# Front_panel.net
KiCad netlist of a schematic drawn in Altium Designer
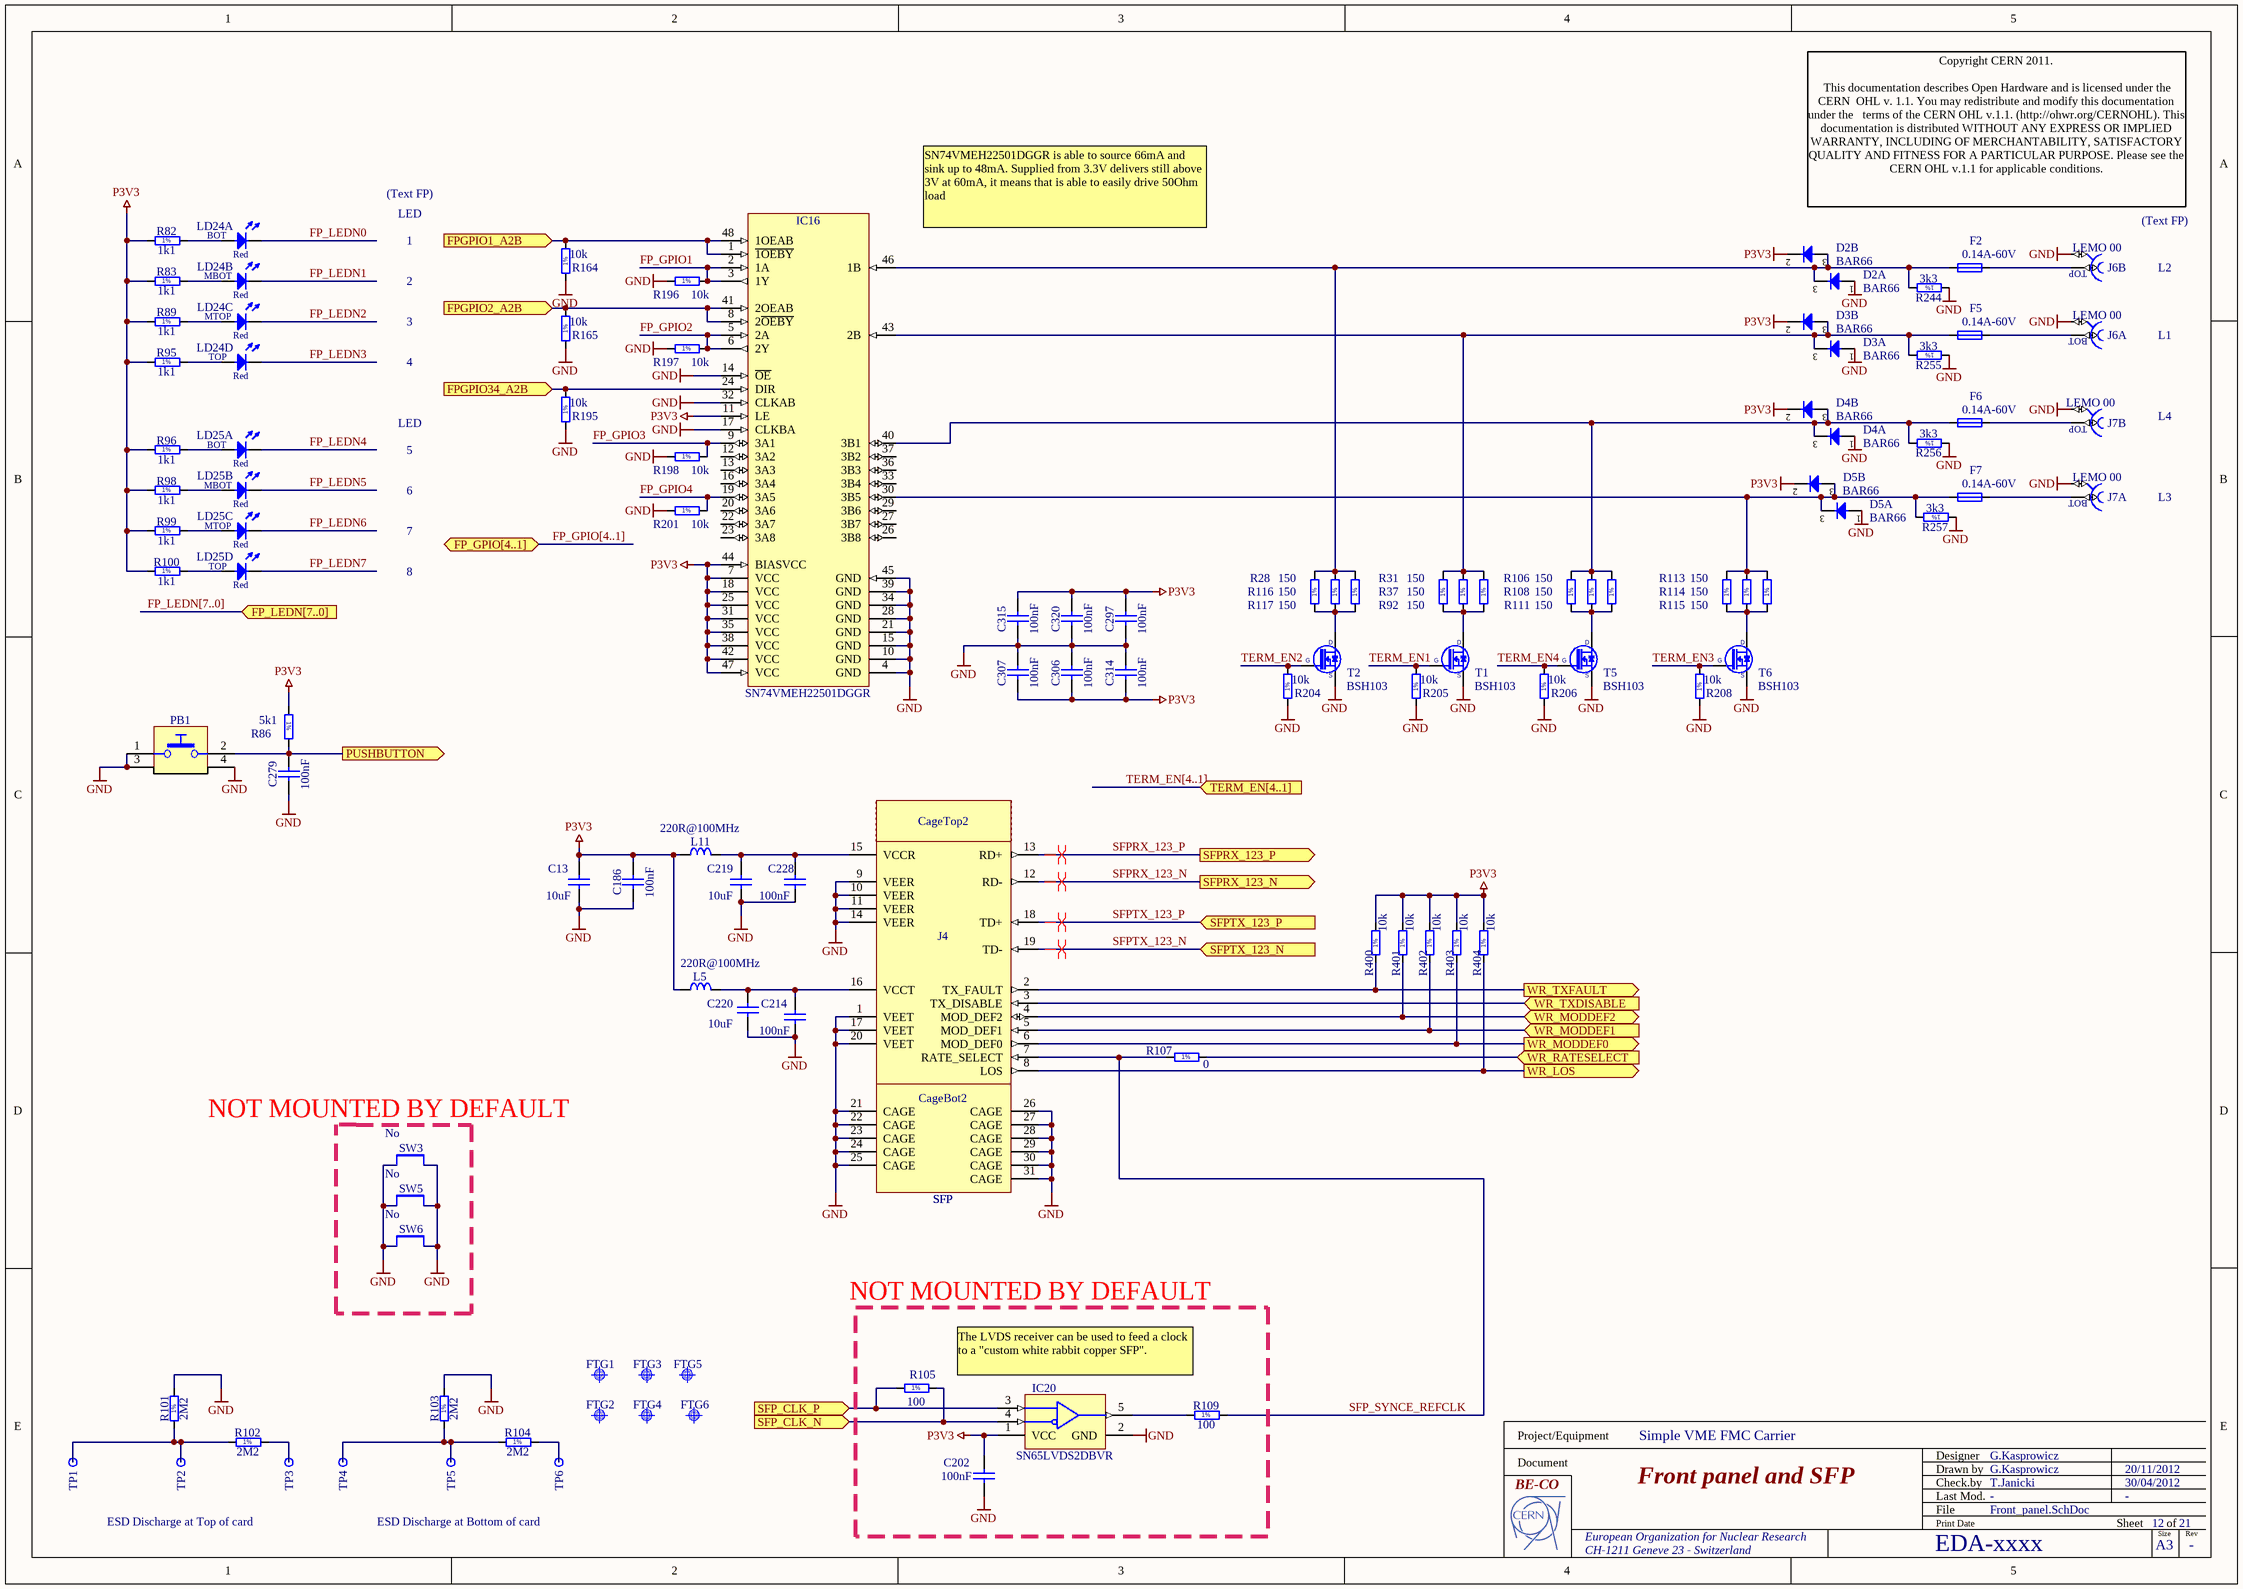
[diagram p0: Front_panel.SchDoc]

(export (version "E")
  (design (tool "Eeschema 10.0.6"))
  (components
    (comp (ref "C13")
      (value "10uF")
      (footprint "CAPC3225X270N")
      (description "Non-polarised capacitor")
      (fields (field (name "PART NUMBER") "CC1210_10UF_25V_10%_X7R") (field (name "VOLTAGE") "25V"))
      (libsource (lib "Capacitors") (part "Capacitor - non polarized"))
    )
    (comp (ref "C186")
      (value "100nF")
      (footprint "CAPC1005X55N")
      (description "Non-polarised capacitor")
      (fields (field (name "PART NUMBER") "CC0402_100NF_16V_10%_X7R") (field (name "VOLTAGE") "16V"))
      (libsource (lib "Capacitors") (part "Capacitor - non polarized"))
    )
    (comp (ref "C202")
      (value "100nF")
      (footprint "CAPC1005X55N")
      (description "Non-polarised capacitor")
      (fields (field (name "PART NUMBER") "CC0402_100NF_16V_10%_X7R") (field (name "VOLTAGE") "16V"))
      (libsource (lib "Capacitors") (part "Capacitor - non polarized"))
    )
    (comp (ref "C214")
      (value "100nF")
      (footprint "CAPC1005X55N")
      (description "Non-polarised capacitor")
      (fields (field (name "PART NUMBER") "CC0402_100NF_16V_10%_X7R") (field (name "VOLTAGE") "16V"))
      (libsource (lib "Capacitors") (part "Capacitor - non polarized"))
    )
    (comp (ref "C219")
      (value "10uF")
      (footprint "CAPC3225X270N")
      (description "Non-polarised capacitor")
      (fields (field (name "PART NUMBER") "CC1210_10UF_25V_10%_X7R") (field (name "VOLTAGE") "25V"))
      (libsource (lib "Capacitors") (part "Capacitor - non polarized"))
    )
    (comp (ref "C220")
      (value "10uF")
      (footprint "CAPC3225X270N")
      (description "Non-polarised capacitor")
      (fields (field (name "PART NUMBER") "CC1210_10UF_25V_10%_X7R") (field (name "VOLTAGE") "25V"))
      (libsource (lib "Capacitors") (part "Capacitor - non polarized"))
    )
    (comp (ref "C228")
      (value "100nF")
      (footprint "CAPC1005X55N")
      (description "Non-polarised capacitor")
      (fields (field (name "PART NUMBER") "CC0402_100NF_16V_10%_X7R") (field (name "VOLTAGE") "16V"))
      (libsource (lib "Capacitors") (part "Capacitor - non polarized"))
    )
    (comp (ref "C279")
      (value "100nF")
      (footprint "CAPC1005X55N")
      (description "Non-polarised capacitor")
      (fields (field (name "PART NUMBER") "CC0402_100NF_16V_10%_X7R") (field (name "VOLTAGE") "16V"))
      (libsource (lib "Capacitors") (part "Capacitor - non polarized"))
    )
    (comp (ref "C297")
      (value "100nF")
      (footprint "CAPC1005X55N")
      (description "Non-polarised capacitor")
      (fields (field (name "PART NUMBER") "CC0402_100NF_16V_10%_X7R") (field (name "VOLTAGE") "16V"))
      (libsource (lib "Capacitors") (part "Capacitor - non polarized"))
    )
    (comp (ref "C306")
      (value "100nF")
      (footprint "CAPC1005X55N")
      (description "Non-polarised capacitor")
      (fields (field (name "PART NUMBER") "CC0402_100NF_16V_10%_X7R") (field (name "VOLTAGE") "16V"))
      (libsource (lib "Capacitors") (part "Capacitor - non polarized"))
    )
    (comp (ref "C307")
      (value "100nF")
      (footprint "CAPC1005X55N")
      (description "Non-polarised capacitor")
      (fields (field (name "PART NUMBER") "CC0402_100NF_16V_10%_X7R") (field (name "VOLTAGE") "16V"))
      (libsource (lib "Capacitors") (part "Capacitor - non polarized"))
    )
    (comp (ref "C314")
      (value "100nF")
      (footprint "CAPC1005X55N")
      (description "Non-polarised capacitor")
      (fields (field (name "PART NUMBER") "CC0402_100NF_16V_10%_X7R") (field (name "VOLTAGE") "16V"))
      (libsource (lib "Capacitors") (part "Capacitor - non polarized"))
    )
    (comp (ref "C315")
      (value "100nF")
      (footprint "CAPC1005X55N")
      (description "Non-polarised capacitor")
      (fields (field (name "PART NUMBER") "CC0402_100NF_16V_10%_X7R") (field (name "VOLTAGE") "16V"))
      (libsource (lib "Capacitors") (part "Capacitor - non polarized"))
    )
    (comp (ref "C320")
      (value "100nF")
      (footprint "CAPC1005X55N")
      (description "Non-polarised capacitor")
      (fields (field (name "PART NUMBER") "CC0402_100NF_16V_10%_X7R") (field (name "VOLTAGE") "16V"))
      (libsource (lib "Capacitors") (part "Capacitor - non polarized"))
    )
    (comp (ref "CageBot2")
      (value "SFP")
      (footprint "TYCO_6367034-1")
      (description "SFP  Cage Bottom (Small Form-factor Pluggable)")
      (fields (field (name "PART NUMBER") "TYCO_6367034-1") (field (name "MANUFACTURER") "TYCO ELECTRONICS"))
      (libsource (lib "Connectors") (part "SFPx1_Cage Bottom"))
    )
    (comp (ref "CageTop2")
      (value "SFP")
      (footprint "TYCO_6367035-1")
      (description "SFP  Cage Top (Small Form-factor Pluggable)")
      (fields (field (name "PART NUMBER") "TYCO_6367035-1") (field (name "MANUFACTURER") "TYCO ELECTRONICS"))
      (libsource (lib "Connectors") (part "SFPx1_Cage Top"))
    )
    (comp (ref "D2")
      (value "BAR66")
      (footprint "SOT95P240X110-3N")
      (description "Serial Diode")
      (fields (field (name "VOLTAGE") "150V") (field (name "POWER") "250mA"))
      (libsource (lib "ICs And Semiconductors") (part "Diode x2 A1C3_A3C2"))
    )
    (comp (ref "D3")
      (value "BAR66")
      (footprint "SOT95P240X110-3N")
      (description "Serial Diode")
      (fields (field (name "VOLTAGE") "150V") (field (name "POWER") "250mA"))
      (libsource (lib "ICs And Semiconductors") (part "Diode x2 A1C3_A3C2"))
    )
    (comp (ref "D4")
      (value "BAR66")
      (footprint "SOT95P240X110-3N")
      (description "Serial Diode")
      (fields (field (name "VOLTAGE") "150V") (field (name "POWER") "250mA"))
      (libsource (lib "ICs And Semiconductors") (part "Diode x2 A1C3_A3C2"))
    )
    (comp (ref "D5")
      (value "BAR66")
      (footprint "SOT95P240X110-3N")
      (description "Serial Diode")
      (fields (field (name "VOLTAGE") "150V") (field (name "POWER") "250mA"))
      (libsource (lib "ICs And Semiconductors") (part "Diode x2 A1C3_A3C2"))
    )
    (comp (ref "F2")
      (value "0.14A-60V")
      (footprint "FUSRC4632X90N")
      (description "Fuse")
      (fields
        (field (name "PART NUMBER") "FUSR1812_TYCO-miniSMD0114F")
        (field (name "MANUFACTURER") "TYCO ELECTRONICS")
      )
      (libsource (lib "Eletro-mechanical") (part "Fuse"))
    )
    (comp (ref "F5")
      (value "0.14A-60V")
      (footprint "FUSRC4632X90N")
      (description "Fuse")
      (fields
        (field (name "PART NUMBER") "FUSR1812_TYCO-miniSMD0114F")
        (field (name "MANUFACTURER") "TYCO ELECTRONICS")
      )
      (libsource (lib "Eletro-mechanical") (part "Fuse"))
    )
    (comp (ref "F6")
      (value "0.14A-60V")
      (footprint "FUSRC4632X90N")
      (description "Fuse")
      (fields
        (field (name "PART NUMBER") "FUSR1812_TYCO-miniSMD0114F")
        (field (name "MANUFACTURER") "TYCO ELECTRONICS")
      )
      (libsource (lib "Eletro-mechanical") (part "Fuse"))
    )
    (comp (ref "F7")
      (value "0.14A-60V")
      (footprint "FUSRC4632X90N")
      (description "Fuse")
      (fields
        (field (name "PART NUMBER") "FUSR1812_TYCO-miniSMD0114F")
        (field (name "MANUFACTURER") "TYCO ELECTRONICS")
      )
      (libsource (lib "Eletro-mechanical") (part "Fuse"))
    )
    (comp (ref "FTG1")
      (value "Use only in PCB")
      (footprint "FIDUCIAL_TOP_S100-200")
      (description "Fiducial Target")
      (fields (field (name "PART NUMBER") "FIDUCIAL_TARGET_S100-200"))
      (libsource (lib "Eletro-mechanical") (part "Fiducial Target"))
    )
    (comp (ref "FTG2")
      (value "Use only in PCB")
      (footprint "FIDUCIAL_TOP_S100-200")
      (description "Fiducial Target")
      (fields (field (name "PART NUMBER") "FIDUCIAL_TARGET_S100-200"))
      (libsource (lib "Eletro-mechanical") (part "Fiducial Target"))
    )
    (comp (ref "FTG3")
      (value "Use only in PCB")
      (footprint "FIDUCIAL_TOP_S100-200")
      (description "Fiducial Target")
      (fields (field (name "PART NUMBER") "FIDUCIAL_TARGET_S100-200"))
      (libsource (lib "Eletro-mechanical") (part "Fiducial Target"))
    )
    (comp (ref "FTG4")
      (value "Use only in PCB")
      (footprint "FIDUCIAL_TOP_S100-200")
      (description "Fiducial Target")
      (fields (field (name "PART NUMBER") "FIDUCIAL_TARGET_S100-200"))
      (libsource (lib "Eletro-mechanical") (part "Fiducial Target"))
    )
    (comp (ref "FTG5")
      (value "Use only in PCB")
      (footprint "FIDUCIAL_TOP_S100-200")
      (description "Fiducial Target")
      (fields (field (name "PART NUMBER") "FIDUCIAL_TARGET_S100-200"))
      (libsource (lib "Eletro-mechanical") (part "Fiducial Target"))
    )
    (comp (ref "FTG6")
      (value "Use only in PCB")
      (footprint "FIDUCIAL_TOP_S100-200")
      (description "Fiducial Target")
      (fields (field (name "PART NUMBER") "FIDUCIAL_TARGET_S100-200"))
      (libsource (lib "Eletro-mechanical") (part "Fiducial Target"))
    )
    (comp (ref "IC16")
      (value "SN74VMEH22501DGGR")
      (footprint "SOP50P810X120-48N")
      (description "8-Bit Universal Bus Transceiver and Two 1-Bit Bus Transceivers with 3-State Outputs")
      (fields (field (name "MANUFACTURER") "TEXAS INSTRUMENTS"))
      (libsource (lib "ICs And Semiconductors") (part "74VMEH22501"))
    )
    (comp (ref "IC20")
      (value "SN65LVDS2DBVR")
      (footprint "SOT95P280X145-5N")
      (description "High-Speed Differential Line Receiver")
      (fields (field (name "MANUFACTURER") "TEXAS INSTRUMENTS"))
      (libsource (lib "ICs And Semiconductors") (part "SN65LVDS2DBVR"))
    )
    (comp (ref "J4")
      (value "SFP")
      (footprint "TYCO_1367073-1")
      (description "20 Position SFP  Connector (Small Form-factor Pluggable)")
      (fields (field (name "PART NUMBER") "TYCO_1367073-1") (field (name "MANUFACTURER") "TYCO ELECTRONICS"))
      (libsource (lib "Connectors") (part "SFPx1"))
    )
    (comp (ref "J6")
      (value "LEMO 00")
      (footprint "LEMO_EPY.00.250.NTNY")
      (description "Dual Female Coax 1-2 Common Shield 3")
      (fields (field (name "PART NUMBER") "LEMO_EPY.00.250.NTNY") (field (name "MANUFACTURER") "LEMO"))
      (libsource (lib "Connectors") (part "LEMO_EPY.00.250.NTN"))
    )
    (comp (ref "J7")
      (value "LEMO 00")
      (footprint "LEMO_EPY.00.250.NTNY")
      (description "Dual Female Coax 1-2 Common Shield 3")
      (fields (field (name "PART NUMBER") "LEMO_EPY.00.250.NTNY") (field (name "MANUFACTURER") "LEMO"))
      (libsource (lib "Connectors") (part "LEMO_EPY.00.250.NTN"))
    )
    (comp (ref "L5")
      (value "220R@100MHz")
      (footprint "INDC2012X105N")
      (description "Inductor")
      (fields (field (name "PART NUMBER") "IND0805_MURATA_BLM21PG221SN1D") (field (name "POWER") "2A"))
      (libsource (lib "Inductors & Transformers") (part "Inductor"))
    )
    (comp (ref "L11")
      (value "220R@100MHz")
      (footprint "INDC2012X105N")
      (description "Inductor")
      (fields (field (name "PART NUMBER") "IND0805_MURATA_BLM21PG221SN1D") (field (name "POWER") "2A"))
      (libsource (lib "Inductors & Transformers") (part "Inductor"))
    )
    (comp (ref "LD24")
      (value "HE Red")
      (footprint "LED_BIVAR_H485CHDL")
      (description "LED x4 Red 1C2A-BOT_3C4A_5C6A_7C8A-TOP")
      (fields (field (name "PART NUMBER") "LED_BIVAR_H485CHDL") (field (name "MANUFACTURER") "BIVAR"))
      (libsource (lib "ICs And Semiconductors") (part "LED x4 Red 1C2A-BOT_3C4A_5C6A_7C8A-TOP"))
    )
    (comp (ref "LD25")
      (value "HE Red")
      (footprint "LED_BIVAR_H485CHDL")
      (description "LED x4 Red 1C2A-BOT_3C4A_5C6A_7C8A-TOP")
      (fields (field (name "PART NUMBER") "LED_BIVAR_H485CHDL") (field (name "MANUFACTURER") "BIVAR"))
      (libsource (lib "ICs And Semiconductors") (part "LED x4 Red 1C2A-BOT_3C4A_5C6A_7C8A-TOP"))
    )
    (comp (ref "PB1")
      (value "Push Button")
      (footprint "PB_ALPS_SKHHLQA010")
      (description "Push-Button Switch SPDT")
      (fields (field (name "PART NUMBER") "PB_ALPS_SKHHLQA010") (field (name "MANUFACTURER") "ALPS"))
      (libsource (lib "Eletro-mechanical") (part "PB SPST 1NO-2NO 34CASE"))
    )
    (comp (ref "R28")
      (value "150")
      (footprint "RESC3216X65N")
      (description "Resistor - 1%")
      (fields (field (name "PART NUMBER") "R1206_150R_1%_0.25W_100PPM") (field (name "POWER") "0.25W"))
      (libsource (lib "Resistors") (part "Resistor - 1%"))
    )
    (comp (ref "R31")
      (value "150")
      (footprint "RESC3216X65N")
      (description "Resistor - 1%")
      (fields (field (name "PART NUMBER") "R1206_150R_1%_0.25W_100PPM") (field (name "POWER") "0.25W"))
      (libsource (lib "Resistors") (part "Resistor - 1%"))
    )
    (comp (ref "R37")
      (value "150")
      (footprint "RESC3216X65N")
      (description "Resistor - 1%")
      (fields (field (name "PART NUMBER") "R1206_150R_1%_0.25W_100PPM") (field (name "POWER") "0.25W"))
      (libsource (lib "Resistors") (part "Resistor - 1%"))
    )
    (comp (ref "R82")
      (value "1k1")
      (footprint "RESC1608X55N")
      (description "Resistor - 1%")
      (fields (field (name "PART NUMBER") "R0603_1K1_1%_0.1W_100PPM") (field (name "POWER") "0.1W"))
      (libsource (lib "Resistors") (part "Resistor - 1%"))
    )
    (comp (ref "R83")
      (value "1k1")
      (footprint "RESC1608X55N")
      (description "Resistor - 1%")
      (fields (field (name "PART NUMBER") "R0603_1K1_1%_0.1W_100PPM") (field (name "POWER") "0.1W"))
      (libsource (lib "Resistors") (part "Resistor - 1%"))
    )
    (comp (ref "R86")
      (value "5k1")
      (footprint "RESC1608X55N")
      (description "Resistor - 1%")
      (fields (field (name "PART NUMBER") "R0603_5K1_1%_0.1W_100PPM") (field (name "POWER") "0.1W"))
      (libsource (lib "Resistors") (part "Resistor - 1%"))
    )
    (comp (ref "R89")
      (value "1k1")
      (footprint "RESC1608X55N")
      (description "Resistor - 1%")
      (fields (field (name "PART NUMBER") "R0603_1K1_1%_0.1W_100PPM") (field (name "POWER") "0.1W"))
      (libsource (lib "Resistors") (part "Resistor - 1%"))
    )
    (comp (ref "R92")
      (value "150")
      (footprint "RESC3216X65N")
      (description "Resistor - 1%")
      (fields (field (name "PART NUMBER") "R1206_150R_1%_0.25W_100PPM") (field (name "POWER") "0.25W"))
      (libsource (lib "Resistors") (part "Resistor - 1%"))
    )
    (comp (ref "R95")
      (value "1k1")
      (footprint "RESC1608X55N")
      (description "Resistor - 1%")
      (fields (field (name "PART NUMBER") "R0603_1K1_1%_0.1W_100PPM") (field (name "POWER") "0.1W"))
      (libsource (lib "Resistors") (part "Resistor - 1%"))
    )
    (comp (ref "R96")
      (value "1k1")
      (footprint "RESC1608X55N")
      (description "Resistor - 1%")
      (fields (field (name "PART NUMBER") "R0603_1K1_1%_0.1W_100PPM") (field (name "POWER") "0.1W"))
      (libsource (lib "Resistors") (part "Resistor - 1%"))
    )
    (comp (ref "R98")
      (value "1k1")
      (footprint "RESC1608X55N")
      (description "Resistor - 1%")
      (fields (field (name "PART NUMBER") "R0603_1K1_1%_0.1W_100PPM") (field (name "POWER") "0.1W"))
      (libsource (lib "Resistors") (part "Resistor - 1%"))
    )
    (comp (ref "R99")
      (value "1k1")
      (footprint "RESC1608X55N")
      (description "Resistor - 1%")
      (fields (field (name "PART NUMBER") "R0603_1K1_1%_0.1W_100PPM") (field (name "POWER") "0.1W"))
      (libsource (lib "Resistors") (part "Resistor - 1%"))
    )
    (comp (ref "R100")
      (value "1k1")
      (footprint "RESC1608X55N")
      (description "Resistor - 1%")
      (fields (field (name "PART NUMBER") "R0603_1K1_1%_0.1W_100PPM") (field (name "POWER") "0.1W"))
      (libsource (lib "Resistors") (part "Resistor - 1%"))
    )
    (comp (ref "R101")
      (value "2M2")
      (footprint "RESC2012X60N")
      (description "Resistor - 1%")
      (fields (field (name "PART NUMBER") "R0805_2M2_1%_0.125W_100PPM") (field (name "POWER") "0.125W"))
      (libsource (lib "Resistors") (part "Resistor - 1%"))
    )
    (comp (ref "R102")
      (value "2M2")
      (footprint "RESC2012X60N")
      (description "Resistor - 1%")
      (fields (field (name "PART NUMBER") "R0805_2M2_1%_0.125W_100PPM") (field (name "POWER") "0.125W"))
      (libsource (lib "Resistors") (part "Resistor - 1%"))
    )
    (comp (ref "R103")
      (value "2M2")
      (footprint "RESC2012X60N")
      (description "Resistor - 1%")
      (fields (field (name "PART NUMBER") "R0805_2M2_1%_0.125W_100PPM") (field (name "POWER") "0.125W"))
      (libsource (lib "Resistors") (part "Resistor - 1%"))
    )
    (comp (ref "R104")
      (value "2M2")
      (footprint "RESC2012X60N")
      (description "Resistor - 1%")
      (fields (field (name "PART NUMBER") "R0805_2M2_1%_0.125W_100PPM") (field (name "POWER") "0.125W"))
      (libsource (lib "Resistors") (part "Resistor - 1%"))
    )
    (comp (ref "R105")
      (value "100")
      (footprint "RESC1608X55N")
      (description "Resistor - 1%")
      (fields (field (name "PART NUMBER") "R0603_100R_1%_0.1W_100PPM") (field (name "POWER") "0.1W"))
      (libsource (lib "Resistors") (part "Resistor - 1%"))
    )
    (comp (ref "R106")
      (value "150")
      (footprint "RESC3216X65N")
      (description "Resistor - 1%")
      (fields (field (name "PART NUMBER") "R1206_150R_1%_0.25W_100PPM") (field (name "POWER") "0.25W"))
      (libsource (lib "Resistors") (part "Resistor - 1%"))
    )
    (comp (ref "R107")
      (value "0")
      (footprint "RESC1608X55N")
      (description "Resistor - 1%")
      (fields (field (name "PART NUMBER") "R0603_0R_JUMPER") (field (name "MANUFACTURER") "GENERIC"))
      (libsource (lib "Resistors") (part "Resistor - 1%"))
    )
    (comp (ref "R108")
      (value "150")
      (footprint "RESC3216X65N")
      (description "Resistor - 1%")
      (fields (field (name "PART NUMBER") "R1206_150R_1%_0.25W_100PPM") (field (name "POWER") "0.25W"))
      (libsource (lib "Resistors") (part "Resistor - 1%"))
    )
    (comp (ref "R109")
      (value "100")
      (footprint "RESC1608X55N")
      (description "Resistor - 1%")
      (fields (field (name "PART NUMBER") "R0603_100R_1%_0.1W_100PPM") (field (name "POWER") "0.1W"))
      (libsource (lib "Resistors") (part "Resistor - 1%"))
    )
    (comp (ref "R111")
      (value "150")
      (footprint "RESC3216X65N")
      (description "Resistor - 1%")
      (fields (field (name "PART NUMBER") "R1206_150R_1%_0.25W_100PPM") (field (name "POWER") "0.25W"))
      (libsource (lib "Resistors") (part "Resistor - 1%"))
    )
    (comp (ref "R113")
      (value "150")
      (footprint "RESC3216X65N")
      (description "Resistor - 1%")
      (fields (field (name "PART NUMBER") "R1206_150R_1%_0.25W_100PPM") (field (name "POWER") "0.25W"))
      (libsource (lib "Resistors") (part "Resistor - 1%"))
    )
    (comp (ref "R114")
      (value "150")
      (footprint "RESC3216X65N")
      (description "Resistor - 1%")
      (fields (field (name "PART NUMBER") "R1206_150R_1%_0.25W_100PPM") (field (name "POWER") "0.25W"))
      (libsource (lib "Resistors") (part "Resistor - 1%"))
    )
    (comp (ref "R115")
      (value "150")
      (footprint "RESC3216X65N")
      (description "Resistor - 1%")
      (fields (field (name "PART NUMBER") "R1206_150R_1%_0.25W_100PPM") (field (name "POWER") "0.25W"))
      (libsource (lib "Resistors") (part "Resistor - 1%"))
    )
    (comp (ref "R116")
      (value "150")
      (footprint "RESC3216X65N")
      (description "Resistor - 1%")
      (fields (field (name "PART NUMBER") "R1206_150R_1%_0.25W_100PPM") (field (name "POWER") "0.25W"))
      (libsource (lib "Resistors") (part "Resistor - 1%"))
    )
    (comp (ref "R117")
      (value "150")
      (footprint "RESC3216X65N")
      (description "Resistor - 1%")
      (fields (field (name "PART NUMBER") "R1206_150R_1%_0.25W_100PPM") (field (name "POWER") "0.25W"))
      (libsource (lib "Resistors") (part "Resistor - 1%"))
    )
    (comp (ref "R164")
      (value "10k")
      (footprint "RESC1608X55N")
      (description "Resistor - 1%")
      (fields (field (name "PART NUMBER") "R0603_10K_1%_0.1W_100PPM") (field (name "POWER") "0.1W"))
      (libsource (lib "Resistors") (part "Resistor - 1%"))
    )
    (comp (ref "R165")
      (value "10k")
      (footprint "RESC1608X55N")
      (description "Resistor - 1%")
      (fields (field (name "PART NUMBER") "R0603_10K_1%_0.1W_100PPM") (field (name "POWER") "0.1W"))
      (libsource (lib "Resistors") (part "Resistor - 1%"))
    )
    (comp (ref "R195")
      (value "10k")
      (footprint "RESC1608X55N")
      (description "Resistor - 1%")
      (fields (field (name "PART NUMBER") "R0603_10K_1%_0.1W_100PPM") (field (name "POWER") "0.1W"))
      (libsource (lib "Resistors") (part "Resistor - 1%"))
    )
    (comp (ref "R196")
      (value "10k")
      (footprint "RESC1608X55N")
      (description "Resistor - 1%")
      (fields (field (name "PART NUMBER") "R0603_10K_1%_0.1W_100PPM") (field (name "POWER") "0.1W"))
      (libsource (lib "Resistors") (part "Resistor - 1%"))
    )
    (comp (ref "R197")
      (value "10k")
      (footprint "RESC1608X55N")
      (description "Resistor - 1%")
      (fields (field (name "PART NUMBER") "R0603_10K_1%_0.1W_100PPM") (field (name "POWER") "0.1W"))
      (libsource (lib "Resistors") (part "Resistor - 1%"))
    )
    (comp (ref "R198")
      (value "10k")
      (footprint "RESC1608X55N")
      (description "Resistor - 1%")
      (fields (field (name "PART NUMBER") "R0603_10K_1%_0.1W_100PPM") (field (name "POWER") "0.1W"))
      (libsource (lib "Resistors") (part "Resistor - 1%"))
    )
    (comp (ref "R201")
      (value "10k")
      (footprint "RESC1608X55N")
      (description "Resistor - 1%")
      (fields (field (name "PART NUMBER") "R0603_10K_1%_0.1W_100PPM") (field (name "POWER") "0.1W"))
      (libsource (lib "Resistors") (part "Resistor - 1%"))
    )
    (comp (ref "R204")
      (value "10k")
      (footprint "RESC1608X55N")
      (description "Resistor - 1%")
      (fields (field (name "PART NUMBER") "R0603_10K_1%_0.1W_100PPM") (field (name "POWER") "0.1W"))
      (libsource (lib "Resistors") (part "Resistor - 1%"))
    )
    (comp (ref "R205")
      (value "10k")
      (footprint "RESC1608X55N")
      (description "Resistor - 1%")
      (fields (field (name "PART NUMBER") "R0603_10K_1%_0.1W_100PPM") (field (name "POWER") "0.1W"))
      (libsource (lib "Resistors") (part "Resistor - 1%"))
    )
    (comp (ref "R206")
      (value "10k")
      (footprint "RESC1608X55N")
      (description "Resistor - 1%")
      (fields (field (name "PART NUMBER") "R0603_10K_1%_0.1W_100PPM") (field (name "POWER") "0.1W"))
      (libsource (lib "Resistors") (part "Resistor - 1%"))
    )
    (comp (ref "R208")
      (value "10k")
      (footprint "RESC1608X55N")
      (description "Resistor - 1%")
      (fields (field (name "PART NUMBER") "R0603_10K_1%_0.1W_100PPM") (field (name "POWER") "0.1W"))
      (libsource (lib "Resistors") (part "Resistor - 1%"))
    )
    (comp (ref "R244")
      (value "3k3")
      (footprint "RESC1608X55N")
      (description "Resistor - 1%")
      (fields (field (name "PART NUMBER") "R0603_3K3_1%_0.1W_100PPM") (field (name "POWER") "0.1W"))
      (libsource (lib "Resistors") (part "Resistor - 1%"))
    )
    (comp (ref "R255")
      (value "3k3")
      (footprint "RESC1608X55N")
      (description "Resistor - 1%")
      (fields (field (name "PART NUMBER") "R0603_3K3_1%_0.1W_100PPM") (field (name "POWER") "0.1W"))
      (libsource (lib "Resistors") (part "Resistor - 1%"))
    )
    (comp (ref "R256")
      (value "3k3")
      (footprint "RESC1608X55N")
      (description "Resistor - 1%")
      (fields (field (name "PART NUMBER") "R0603_3K3_1%_0.1W_100PPM") (field (name "POWER") "0.1W"))
      (libsource (lib "Resistors") (part "Resistor - 1%"))
    )
    (comp (ref "R257")
      (value "3k3")
      (footprint "RESC1608X55N")
      (description "Resistor - 1%")
      (fields (field (name "PART NUMBER") "R0603_3K3_1%_0.1W_100PPM") (field (name "POWER") "0.1W"))
      (libsource (lib "Resistors") (part "Resistor - 1%"))
    )
    (comp (ref "R400")
      (value "10k")
      (footprint "RESC1608X55N")
      (description "Resistor - 1%")
      (fields (field (name "PART NUMBER") "R0603_10K_1%_0.1W_100PPM") (field (name "POWER") "0.1W"))
      (libsource (lib "Resistors") (part "Resistor - 1%"))
    )
    (comp (ref "R401")
      (value "10k")
      (footprint "RESC1608X55N")
      (description "Resistor - 1%")
      (fields (field (name "PART NUMBER") "R0603_10K_1%_0.1W_100PPM") (field (name "POWER") "0.1W"))
      (libsource (lib "Resistors") (part "Resistor - 1%"))
    )
    (comp (ref "R402")
      (value "10k")
      (footprint "RESC1608X55N")
      (description "Resistor - 1%")
      (fields (field (name "PART NUMBER") "R0603_10K_1%_0.1W_100PPM") (field (name "POWER") "0.1W"))
      (libsource (lib "Resistors") (part "Resistor - 1%"))
    )
    (comp (ref "R403")
      (value "10k")
      (footprint "RESC1608X55N")
      (description "Resistor - 1%")
      (fields (field (name "PART NUMBER") "R0603_10K_1%_0.1W_100PPM") (field (name "POWER") "0.1W"))
      (libsource (lib "Resistors") (part "Resistor - 1%"))
    )
    (comp (ref "R404")
      (value "10k")
      (footprint "RESC1608X55N")
      (description "Resistor - 1%")
      (fields (field (name "PART NUMBER") "R0603_10K_1%_0.1W_100PPM") (field (name "POWER") "0.1W"))
      (libsource (lib "Resistors") (part "Resistor - 1%"))
    )
    (comp (ref "SW3")
      (value "Jumper Type2")
      (footprint "COMATEL_313.0004.0.00.500")
      (description "Jumper 2 pins")
      (fields
        (field (name "PART NUMBER") "COMATEL_313.0004.0.00.500")
        (field (name "MOUNTED") "No")
        (field (name "MANUFACTURER") "KONTEK COMATEL")
      )
      (libsource (lib "Connectors") (part "Jumper Type2"))
    )
    (comp (ref "SW5")
      (value "Jumper Type2")
      (footprint "COMATEL_313.0004.0.00.500")
      (description "Jumper 2 pins")
      (fields
        (field (name "PART NUMBER") "COMATEL_313.0004.0.00.500")
        (field (name "MOUNTED") "No")
        (field (name "MANUFACTURER") "KONTEK COMATEL")
      )
      (libsource (lib "Connectors") (part "Jumper Type2"))
    )
    (comp (ref "SW6")
      (value "Jumper Type2")
      (footprint "COMATEL_313.0004.0.00.500")
      (description "Jumper 2 pins")
      (fields
        (field (name "PART NUMBER") "COMATEL_313.0004.0.00.500")
        (field (name "MOUNTED") "No")
        (field (name "MANUFACTURER") "KONTEK COMATEL")
      )
      (libsource (lib "Connectors") (part "Jumper Type2"))
    )
    (comp (ref "T1")
      (value "BSH103")
      (footprint "SOT95P230X110-3N")
      (description "N-CHANNEL MOSFET WITH DIODE")
      (fields (field (name "MANUFACTURER") "NXP SEMICONDUCTORS"))
      (libsource (lib "ICs And Semiconductors") (part "N-MOSFET-D 1G 2S 3D"))
    )
    (comp (ref "T2")
      (value "BSH103")
      (footprint "SOT95P230X110-3N")
      (description "N-CHANNEL MOSFET WITH DIODE")
      (fields (field (name "MANUFACTURER") "NXP SEMICONDUCTORS"))
      (libsource (lib "ICs And Semiconductors") (part "N-MOSFET-D 1G 2S 3D"))
    )
    (comp (ref "T5")
      (value "BSH103")
      (footprint "SOT95P230X110-3N")
      (description "N-CHANNEL MOSFET WITH DIODE")
      (fields (field (name "MANUFACTURER") "NXP SEMICONDUCTORS"))
      (libsource (lib "ICs And Semiconductors") (part "N-MOSFET-D 1G 2S 3D"))
    )
    (comp (ref "T6")
      (value "BSH103")
      (footprint "SOT95P230X110-3N")
      (description "N-CHANNEL MOSFET WITH DIODE")
      (fields (field (name "MANUFACTURER") "NXP SEMICONDUCTORS"))
      (libsource (lib "ICs And Semiconductors") (part "N-MOSFET-D 1G 2S 3D"))
    )
    (comp (ref "TP1")
      (value "Test Point")
      (footprint "TPS127")
      (fields (field (name "PART NUMBER") "SMD_PAD_1.27X1.27MM"))
      (libsource (lib "Eletro-mechanical") (part "Test Point"))
    )
    (comp (ref "TP2")
      (value "Test Point")
      (footprint "TPS127")
      (fields (field (name "PART NUMBER") "SMD_PAD_1.27X1.27MM"))
      (libsource (lib "Eletro-mechanical") (part "Test Point"))
    )
    (comp (ref "TP3")
      (value "Test Point")
      (footprint "TPS127")
      (fields (field (name "PART NUMBER") "SMD_PAD_1.27X1.27MM"))
      (libsource (lib "Eletro-mechanical") (part "Test Point"))
    )
    (comp (ref "TP4")
      (value "Test Point")
      (footprint "TPS127")
      (fields (field (name "PART NUMBER") "SMD_PAD_1.27X1.27MM"))
      (libsource (lib "Eletro-mechanical") (part "Test Point"))
    )
    (comp (ref "TP5")
      (value "Test Point")
      (footprint "TPS127")
      (fields (field (name "PART NUMBER") "SMD_PAD_1.27X1.27MM"))
      (libsource (lib "Eletro-mechanical") (part "Test Point"))
    )
    (comp (ref "TP6")
      (value "Test Point")
      (footprint "TPS127")
      (fields (field (name "PART NUMBER") "SMD_PAD_1.27X1.27MM"))
      (libsource (lib "Eletro-mechanical") (part "Test Point"))
    )
  )
  (nets
    (net (code "1") (name "/FPGPIO1_A2B") (class "Default")
      (node (ref "IC16") (pin "1") (pinfunction "~{1OEBY}_1") (pintype "input"))
      (node (ref "IC16") (pin "48") (pinfunction "1OEAB_48") (pintype "input"))
      (node (ref "R164") (pin "2") (pinfunction "2_2") (pintype "passive"))
    )
    (net (code "2") (name "/FPGPIO2_A2B") (class "Default")
      (node (ref "IC16") (pin "41") (pinfunction "2OEAB_41") (pintype "input"))
      (node (ref "IC16") (pin "8") (pinfunction "2~{OEBY}_8") (pintype "input"))
      (node (ref "R165") (pin "2") (pinfunction "2_2") (pintype "passive"))
    )
    (net (code "3") (name "/FPGPIO34_A2B") (class "Default")
      (node (ref "IC16") (pin "24") (pinfunction "DIR_24") (pintype "input"))
      (node (ref "R195") (pin "2") (pinfunction "2_2") (pintype "passive"))
    )
    (net (code "4") (name "/FP_GPIO1") (class "Default")
      (node (ref "IC16") (pin "2") (pinfunction "1A_2") (pintype "input"))
      (node (ref "IC16") (pin "3") (pinfunction "1Y_3") (pintype "output"))
      (node (ref "R196") (pin "2") (pinfunction "2_2") (pintype "passive"))
    )
    (net (code "5") (name "/FP_GPIO2") (class "Default")
      (node (ref "IC16") (pin "5") (pinfunction "2A_5") (pintype "input"))
      (node (ref "IC16") (pin "6") (pinfunction "2Y_6") (pintype "output"))
      (node (ref "R197") (pin "2") (pinfunction "2_2") (pintype "passive"))
    )
    (net (code "6") (name "/FP_GPIO3") (class "Default")
      (node (ref "IC16") (pin "9") (pinfunction "3A1_9") (pintype "bidirectional"))
      (node (ref "R198") (pin "2") (pinfunction "2_2") (pintype "passive"))
    )
    (net (code "7") (name "/FP_GPIO4") (class "Default")
      (node (ref "IC16") (pin "19") (pinfunction "3A5_19") (pintype "bidirectional"))
      (node (ref "R201") (pin "2") (pinfunction "2_2") (pintype "passive"))
    )
    (net (code "9") (name "/FP_LEDN0") (class "Default")
      (node (ref "LD24") (pin "1") (pinfunction "C_1") (pintype "passive"))
    )
    (net (code "10") (name "/FP_LEDN1") (class "Default")
      (node (ref "LD24") (pin "3") (pinfunction "C_3") (pintype "passive"))
    )
    (net (code "11") (name "/FP_LEDN2") (class "Default")
      (node (ref "LD24") (pin "5") (pinfunction "C_5") (pintype "passive"))
    )
    (net (code "12") (name "/FP_LEDN3") (class "Default")
      (node (ref "LD24") (pin "7") (pinfunction "C_7") (pintype "passive"))
    )
    (net (code "13") (name "/FP_LEDN4") (class "Default")
      (node (ref "LD25") (pin "1") (pinfunction "C_1") (pintype "passive"))
    )
    (net (code "14") (name "/FP_LEDN5") (class "Default")
      (node (ref "LD25") (pin "3") (pinfunction "C_3") (pintype "passive"))
    )
    (net (code "15") (name "/FP_LEDN6") (class "Default")
      (node (ref "LD25") (pin "5") (pinfunction "C_5") (pintype "passive"))
    )
    (net (code "16") (name "/FP_LEDN7") (class "Default")
      (node (ref "LD25") (pin "7") (pinfunction "C_7") (pintype "passive"))
    )
    (net (code "18") (name "/PUSHBUTTON") (class "Default")
      (node (ref "C279") (pin "2") (pinfunction "2_2") (pintype "passive"))
      (node (ref "PB1") (pin "2") (pinfunction "2_2") (pintype "passive"))
      (node (ref "R86") (pin "2") (pinfunction "2_2") (pintype "passive"))
    )
    (net (code "19") (name "/SFPRX_123_N") (class "Default")
      (node (ref "J4") (pin "12") (pinfunction "RD-_12") (pintype "output"))
    )
    (net (code "20") (name "/SFPRX_123_P") (class "Default")
      (node (ref "J4") (pin "13") (pinfunction "RD+_13") (pintype "output"))
    )
    (net (code "21") (name "/SFPTX_123_N") (class "Default")
      (node (ref "J4") (pin "19") (pinfunction "TD-_19") (pintype "input"))
    )
    (net (code "22") (name "/SFPTX_123_P") (class "Default")
      (node (ref "J4") (pin "18") (pinfunction "TD+_18") (pintype "input"))
    )
    (net (code "23") (name "/SFP_CLK_N") (class "Default")
      (node (ref "IC20") (pin "4") (pinfunction "B_4") (pintype "input"))
      (node (ref "R105") (pin "2") (pinfunction "2_2") (pintype "passive"))
    )
    (net (code "24") (name "/SFP_CLK_P") (class "Default")
      (node (ref "IC20") (pin "3") (pinfunction "A_3") (pintype "input"))
      (node (ref "R105") (pin "1") (pinfunction "1_1") (pintype "passive"))
    )
    (net (code "25") (name "/SFP_SYNCE_REFCLK") (class "Default")
      (node (ref "J4") (pin "7") (pinfunction "RATE_SELECT_7") (pintype "input"))
      (node (ref "R107") (pin "1") (pinfunction "1_1") (pintype "passive"))
      (node (ref "R109") (pin "2") (pinfunction "2_2") (pintype "passive"))
    )
    (net (code "26") (name "/TERM_EN1") (class "Default")
      (node (ref "R205") (pin "2") (pinfunction "2_2") (pintype "passive"))
      (node (ref "T1") (pin "1") (pinfunction "G_1") (pintype "passive"))
    )
    (net (code "27") (name "/TERM_EN2") (class "Default")
      (node (ref "R204") (pin "2") (pinfunction "2_2") (pintype "passive"))
      (node (ref "T2") (pin "1") (pinfunction "G_1") (pintype "passive"))
    )
    (net (code "28") (name "/TERM_EN3") (class "Default")
      (node (ref "R208") (pin "2") (pinfunction "2_2") (pintype "passive"))
      (node (ref "T6") (pin "1") (pinfunction "G_1") (pintype "passive"))
    )
    (net (code "29") (name "/TERM_EN4") (class "Default")
      (node (ref "R206") (pin "2") (pinfunction "2_2") (pintype "passive"))
      (node (ref "T5") (pin "1") (pinfunction "G_1") (pintype "passive"))
    )
    (net (code "31") (name "/WR_LOS") (class "Default")
      (node (ref "J4") (pin "8") (pinfunction "LOS_8") (pintype "output"))
      (node (ref "R404") (pin "1") (pinfunction "1_1") (pintype "passive"))
    )
    (net (code "32") (name "/WR_MODDEF0") (class "Default")
      (node (ref "J4") (pin "6") (pinfunction "MOD_DEF0_6") (pintype "output"))
      (node (ref "R403") (pin "1") (pinfunction "1_1") (pintype "passive"))
    )
    (net (code "33") (name "/WR_MODDEF1") (class "Default")
      (node (ref "J4") (pin "5") (pinfunction "MOD_DEF1_5") (pintype "input"))
      (node (ref "R402") (pin "1") (pinfunction "1_1") (pintype "passive"))
    )
    (net (code "34") (name "/WR_MODDEF2") (class "Default")
      (node (ref "J4") (pin "4") (pinfunction "MOD_DEF2_4") (pintype "bidirectional"))
      (node (ref "R401") (pin "1") (pinfunction "1_1") (pintype "passive"))
    )
    (net (code "35") (name "/WR_RATESELECT") (class "Default")
      (node (ref "R107") (pin "2") (pinfunction "2_2") (pintype "passive"))
    )
    (net (code "36") (name "/WR_TXDISABLE") (class "Default")
      (node (ref "J4") (pin "3") (pinfunction "TX_DISABLE_3") (pintype "input"))
    )
    (net (code "37") (name "/WR_TXFAULT") (class "Default")
      (node (ref "J4") (pin "2") (pinfunction "TX_FAULT_2") (pintype "output"))
      (node (ref "R400") (pin "1") (pinfunction "1_1") (pintype "passive"))
    )
    (net (code "38") (name "GND") (class "Default")
      (node (ref "C13") (pin "2") (pinfunction "2_2") (pintype "passive"))
      (node (ref "C186") (pin "2") (pinfunction "2_2") (pintype "passive"))
      (node (ref "C202") (pin "1") (pinfunction "1_1") (pintype "passive"))
      (node (ref "C214") (pin "2") (pinfunction "2_2") (pintype "passive"))
      (node (ref "C219") (pin "2") (pinfunction "2_2") (pintype "passive"))
      (node (ref "C220") (pin "2") (pinfunction "2_2") (pintype "passive"))
      (node (ref "C228") (pin "2") (pinfunction "2_2") (pintype "passive"))
      (node (ref "C279") (pin "1") (pinfunction "1_1") (pintype "passive"))
      (node (ref "C297") (pin "1") (pinfunction "1_1") (pintype "passive"))
      (node (ref "C306") (pin "2") (pinfunction "2_2") (pintype "passive"))
      (node (ref "C307") (pin "2") (pinfunction "2_2") (pintype "passive"))
      (node (ref "C314") (pin "2") (pinfunction "2_2") (pintype "passive"))
      (node (ref "C315") (pin "1") (pinfunction "1_1") (pintype "passive"))
      (node (ref "C320") (pin "1") (pinfunction "1_1") (pintype "passive"))
      (node (ref "CageBot2") (pin "21") (pinfunction "CAGE_21") (pintype "power_in"))
      (node (ref "CageBot2") (pin "22") (pinfunction "CAGE_22") (pintype "power_in"))
      (node (ref "CageBot2") (pin "23") (pinfunction "CAGE_23") (pintype "power_in"))
      (node (ref "CageBot2") (pin "24") (pinfunction "CAGE_24") (pintype "power_in"))
      (node (ref "CageBot2") (pin "25") (pinfunction "CAGE_25") (pintype "power_in"))
      (node (ref "CageBot2") (pin "26") (pinfunction "CAGE_26") (pintype "power_in"))
      (node (ref "CageBot2") (pin "27") (pinfunction "CAGE_27") (pintype "power_in"))
      (node (ref "CageBot2") (pin "28") (pinfunction "CAGE_28") (pintype "power_in"))
      (node (ref "CageBot2") (pin "29") (pinfunction "CAGE_29") (pintype "power_in"))
      (node (ref "CageBot2") (pin "30") (pinfunction "CAGE_30") (pintype "power_in"))
      (node (ref "CageBot2") (pin "31") (pinfunction "CAGE_31") (pintype "power_in"))
      (node (ref "D2") (pin "1") (pinfunction "A_1") (pintype "passive"))
      (node (ref "D3") (pin "1") (pinfunction "A_1") (pintype "passive"))
      (node (ref "D4") (pin "1") (pinfunction "A_1") (pintype "passive"))
      (node (ref "D5") (pin "1") (pinfunction "A_1") (pintype "passive"))
      (node (ref "IC16") (pin "10") (pinfunction "GND_10") (pintype "power_in"))
      (node (ref "IC16") (pin "14") (pinfunction "~{OE}_14") (pintype "input"))
      (node (ref "IC16") (pin "15") (pinfunction "GND_15") (pintype "power_in"))
      (node (ref "IC16") (pin "17") (pinfunction "CLKBA_17") (pintype "input"))
      (node (ref "IC16") (pin "21") (pinfunction "GND_21") (pintype "power_in"))
      (node (ref "IC16") (pin "28") (pinfunction "GND_28") (pintype "power_in"))
      (node (ref "IC16") (pin "32") (pinfunction "CLKAB_32") (pintype "input"))
      (node (ref "IC16") (pin "34") (pinfunction "GND_34") (pintype "power_in"))
      (node (ref "IC16") (pin "39") (pinfunction "GND_39") (pintype "power_in"))
      (node (ref "IC16") (pin "4") (pinfunction "GND_4") (pintype "power_in"))
      (node (ref "IC16") (pin "45") (pinfunction "GND_45") (pintype "input"))
      (node (ref "IC20") (pin "2") (pinfunction "GND_2") (pintype "power_in"))
      (node (ref "J4") (pin "1") (pinfunction "VEET_1") (pintype "power_in"))
      (node (ref "J4") (pin "10") (pinfunction "VEER_10") (pintype "power_in"))
      (node (ref "J4") (pin "11") (pinfunction "VEER_11") (pintype "power_in"))
      (node (ref "J4") (pin "14") (pinfunction "VEER_14") (pintype "power_in"))
      (node (ref "J4") (pin "17") (pinfunction "VEET_17") (pintype "power_in"))
      (node (ref "J4") (pin "20") (pinfunction "VEET_20") (pintype "power_in"))
      (node (ref "J4") (pin "9") (pinfunction "VEER_9") (pintype "power_in"))
      (node (ref "J6") (pin "3") (pinfunction "3_3") (pintype "bidirectional"))
      (node (ref "J7") (pin "3") (pinfunction "3_3") (pintype "bidirectional"))
      (node (ref "PB1") (pin "1") (pinfunction "1_1") (pintype "passive"))
      (node (ref "PB1") (pin "3") (pinfunction "3_3") (pintype "passive"))
      (node (ref "PB1") (pin "4") (pinfunction "4_4") (pintype "passive"))
      (node (ref "R101") (pin "2") (pinfunction "2_2") (pintype "passive"))
      (node (ref "R103") (pin "2") (pinfunction "2_2") (pintype "passive"))
      (node (ref "R164") (pin "1") (pinfunction "1_1") (pintype "passive"))
      (node (ref "R165") (pin "1") (pinfunction "1_1") (pintype "passive"))
      (node (ref "R195") (pin "1") (pinfunction "1_1") (pintype "passive"))
      (node (ref "R196") (pin "1") (pinfunction "1_1") (pintype "passive"))
      (node (ref "R197") (pin "1") (pinfunction "1_1") (pintype "passive"))
      (node (ref "R198") (pin "1") (pinfunction "1_1") (pintype "passive"))
      (node (ref "R201") (pin "1") (pinfunction "1_1") (pintype "passive"))
      (node (ref "R204") (pin "1") (pinfunction "1_1") (pintype "passive"))
      (node (ref "R205") (pin "1") (pinfunction "1_1") (pintype "passive"))
      (node (ref "R206") (pin "1") (pinfunction "1_1") (pintype "passive"))
      (node (ref "R208") (pin "1") (pinfunction "1_1") (pintype "passive"))
      (node (ref "R244") (pin "1") (pinfunction "1_1") (pintype "passive"))
      (node (ref "R255") (pin "1") (pinfunction "1_1") (pintype "passive"))
      (node (ref "R256") (pin "1") (pinfunction "1_1") (pintype "passive"))
      (node (ref "R257") (pin "1") (pinfunction "1_1") (pintype "passive"))
      (node (ref "SW3") (pin "1") (pinfunction "1_1") (pintype "bidirectional"))
      (node (ref "SW3") (pin "2") (pinfunction "2_2") (pintype "bidirectional"))
      (node (ref "SW5") (pin "1") (pinfunction "1_1") (pintype "bidirectional"))
      (node (ref "SW5") (pin "2") (pinfunction "2_2") (pintype "bidirectional"))
      (node (ref "SW6") (pin "1") (pinfunction "1_1") (pintype "bidirectional"))
      (node (ref "SW6") (pin "2") (pinfunction "2_2") (pintype "bidirectional"))
      (node (ref "T1") (pin "2") (pinfunction "S_2") (pintype "passive"))
      (node (ref "T2") (pin "2") (pinfunction "S_2") (pintype "passive"))
      (node (ref "T5") (pin "2") (pinfunction "S_2") (pintype "passive"))
      (node (ref "T6") (pin "2") (pinfunction "S_2") (pintype "passive"))
    )
    (net (code "39") (name "Net-(D2A-COMAC)") (class "Default")
      (node (ref "D2") (pin "3") (pinfunction "COMAC_3") (pintype "passive"))
      (node (ref "F2") (pin "1") (pinfunction "1_1") (pintype "passive"))
      (node (ref "IC16") (pin "46") (pinfunction "1B_46") (pintype "input"))
      (node (ref "R116") (pin "2") (pinfunction "2_2") (pintype "passive"))
      (node (ref "R117") (pin "2") (pinfunction "2_2") (pintype "passive"))
      (node (ref "R244") (pin "2") (pinfunction "2_2") (pintype "passive"))
      (node (ref "R28") (pin "2") (pinfunction "2_2") (pintype "passive"))
    )
    (net (code "40") (name "Net-(D3A-COMAC)") (class "Default")
      (node (ref "D3") (pin "3") (pinfunction "COMAC_3") (pintype "passive"))
      (node (ref "F5") (pin "1") (pinfunction "1_1") (pintype "passive"))
      (node (ref "IC16") (pin "43") (pinfunction "2B_43") (pintype "input"))
      (node (ref "R255") (pin "2") (pinfunction "2_2") (pintype "passive"))
      (node (ref "R31") (pin "2") (pinfunction "2_2") (pintype "passive"))
      (node (ref "R37") (pin "2") (pinfunction "2_2") (pintype "passive"))
      (node (ref "R92") (pin "2") (pinfunction "2_2") (pintype "passive"))
    )
    (net (code "41") (name "Net-(D4A-COMAC)") (class "Default")
      (node (ref "D4") (pin "3") (pinfunction "COMAC_3") (pintype "passive"))
      (node (ref "F6") (pin "1") (pinfunction "1_1") (pintype "passive"))
      (node (ref "IC16") (pin "40") (pinfunction "3B1_40") (pintype "bidirectional"))
      (node (ref "R106") (pin "2") (pinfunction "2_2") (pintype "passive"))
      (node (ref "R108") (pin "2") (pinfunction "2_2") (pintype "passive"))
      (node (ref "R111") (pin "2") (pinfunction "2_2") (pintype "passive"))
      (node (ref "R256") (pin "2") (pinfunction "2_2") (pintype "passive"))
    )
    (net (code "42") (name "Net-(D5A-COMAC)") (class "Default")
      (node (ref "D5") (pin "3") (pinfunction "COMAC_3") (pintype "passive"))
      (node (ref "F7") (pin "1") (pinfunction "1_1") (pintype "passive"))
      (node (ref "IC16") (pin "30") (pinfunction "3B5_30") (pintype "bidirectional"))
      (node (ref "R113") (pin "2") (pinfunction "2_2") (pintype "passive"))
      (node (ref "R114") (pin "2") (pinfunction "2_2") (pintype "passive"))
      (node (ref "R115") (pin "2") (pinfunction "2_2") (pintype "passive"))
      (node (ref "R257") (pin "2") (pinfunction "2_2") (pintype "passive"))
    )
    (net (code "43") (name "Net-(F2-Pad2)") (class "Default")
      (node (ref "F2") (pin "2") (pinfunction "2_2") (pintype "passive"))
      (node (ref "J6") (pin "2") (pinfunction "2_2") (pintype "bidirectional"))
    )
    (net (code "44") (name "Net-(F5-Pad2)") (class "Default")
      (node (ref "F5") (pin "2") (pinfunction "2_2") (pintype "passive"))
      (node (ref "J6") (pin "1") (pinfunction "1_1") (pintype "bidirectional"))
    )
    (net (code "45") (name "Net-(F6-Pad2)") (class "Default")
      (node (ref "F6") (pin "2") (pinfunction "2_2") (pintype "passive"))
      (node (ref "J7") (pin "2") (pinfunction "2_2") (pintype "bidirectional"))
    )
    (net (code "46") (name "Net-(F7-Pad2)") (class "Default")
      (node (ref "F7") (pin "2") (pinfunction "2_2") (pintype "passive"))
      (node (ref "J7") (pin "1") (pinfunction "1_1") (pintype "bidirectional"))
    )
    (net (code "47") (name "Net-(IC20-R)") (class "Default")
      (node (ref "IC20") (pin "5") (pinfunction "R_5") (pintype "output"))
      (node (ref "R109") (pin "1") (pinfunction "1_1") (pintype "passive"))
    )
    (net (code "48") (name "Net-(J4-VCCR)") (class "Default")
      (node (ref "C219") (pin "1") (pinfunction "1_1") (pintype "passive"))
      (node (ref "C228") (pin "1") (pinfunction "1_1") (pintype "passive"))
      (node (ref "J4") (pin "15") (pinfunction "VCCR_15") (pintype "power_in"))
      (node (ref "L11") (pin "2") (pinfunction "2_2") (pintype "passive"))
    )
    (net (code "49") (name "Net-(J4-VCCT)") (class "Default")
      (node (ref "C214") (pin "1") (pinfunction "1_1") (pintype "passive"))
      (node (ref "C220") (pin "1") (pinfunction "1_1") (pintype "passive"))
      (node (ref "J4") (pin "16") (pinfunction "VCCT_16") (pintype "power_in"))
      (node (ref "L5") (pin "2") (pinfunction "2_2") (pintype "passive"))
    )
    (net (code "50") (name "Net-(LD24A-A)") (class "Default")
      (node (ref "LD24") (pin "2") (pinfunction "A_2") (pintype "passive"))
      (node (ref "R82") (pin "2") (pinfunction "2_2") (pintype "passive"))
    )
    (net (code "51") (name "Net-(LD24B-A)") (class "Default")
      (node (ref "LD24") (pin "4") (pinfunction "A_4") (pintype "passive"))
      (node (ref "R83") (pin "2") (pinfunction "2_2") (pintype "passive"))
    )
    (net (code "52") (name "Net-(LD24C-A)") (class "Default")
      (node (ref "LD24") (pin "6") (pinfunction "A_6") (pintype "passive"))
      (node (ref "R89") (pin "2") (pinfunction "2_2") (pintype "passive"))
    )
    (net (code "53") (name "Net-(LD24D-A)") (class "Default")
      (node (ref "LD24") (pin "8") (pinfunction "A_8") (pintype "passive"))
      (node (ref "R95") (pin "2") (pinfunction "2_2") (pintype "passive"))
    )
    (net (code "54") (name "Net-(LD25A-A)") (class "Default")
      (node (ref "LD25") (pin "2") (pinfunction "A_2") (pintype "passive"))
      (node (ref "R96") (pin "2") (pinfunction "2_2") (pintype "passive"))
    )
    (net (code "55") (name "Net-(LD25B-A)") (class "Default")
      (node (ref "LD25") (pin "4") (pinfunction "A_4") (pintype "passive"))
      (node (ref "R98") (pin "2") (pinfunction "2_2") (pintype "passive"))
    )
    (net (code "56") (name "Net-(LD25C-A)") (class "Default")
      (node (ref "LD25") (pin "6") (pinfunction "A_6") (pintype "passive"))
      (node (ref "R99") (pin "2") (pinfunction "2_2") (pintype "passive"))
    )
    (net (code "57") (name "Net-(LD25D-A)") (class "Default")
      (node (ref "LD25") (pin "8") (pinfunction "A_8") (pintype "passive"))
      (node (ref "R100") (pin "2") (pinfunction "2_2") (pintype "passive"))
    )
    (net (code "58") (name "Net-(R101-Pad1)") (class "Default")
      (node (ref "R101") (pin "1") (pinfunction "1_1") (pintype "passive"))
      (node (ref "R102") (pin "1") (pinfunction "1_1") (pintype "passive"))
      (node (ref "TP1") (pin "1") (pinfunction "1_1") (pintype "bidirectional"))
      (node (ref "TP2") (pin "1") (pinfunction "1_1") (pintype "bidirectional"))
    )
    (net (code "59") (name "Net-(R102-Pad2)") (class "Default")
      (node (ref "R102") (pin "2") (pinfunction "2_2") (pintype "passive"))
      (node (ref "TP3") (pin "1") (pinfunction "1_1") (pintype "bidirectional"))
    )
    (net (code "60") (name "Net-(R103-Pad1)") (class "Default")
      (node (ref "R103") (pin "1") (pinfunction "1_1") (pintype "passive"))
      (node (ref "R104") (pin "1") (pinfunction "1_1") (pintype "passive"))
      (node (ref "TP4") (pin "1") (pinfunction "1_1") (pintype "bidirectional"))
      (node (ref "TP5") (pin "1") (pinfunction "1_1") (pintype "bidirectional"))
    )
    (net (code "61") (name "Net-(R104-Pad2)") (class "Default")
      (node (ref "R104") (pin "2") (pinfunction "2_2") (pintype "passive"))
      (node (ref "TP6") (pin "1") (pinfunction "1_1") (pintype "bidirectional"))
    )
    (net (code "62") (name "Net-(T1-D)") (class "Default")
      (node (ref "R31") (pin "1") (pinfunction "1_1") (pintype "passive"))
      (node (ref "R37") (pin "1") (pinfunction "1_1") (pintype "passive"))
      (node (ref "R92") (pin "1") (pinfunction "1_1") (pintype "passive"))
      (node (ref "T1") (pin "3") (pinfunction "D_3") (pintype "passive"))
    )
    (net (code "63") (name "Net-(T2-D)") (class "Default")
      (node (ref "R116") (pin "1") (pinfunction "1_1") (pintype "passive"))
      (node (ref "R117") (pin "1") (pinfunction "1_1") (pintype "passive"))
      (node (ref "R28") (pin "1") (pinfunction "1_1") (pintype "passive"))
      (node (ref "T2") (pin "3") (pinfunction "D_3") (pintype "passive"))
    )
    (net (code "64") (name "Net-(T5-D)") (class "Default")
      (node (ref "R106") (pin "1") (pinfunction "1_1") (pintype "passive"))
      (node (ref "R108") (pin "1") (pinfunction "1_1") (pintype "passive"))
      (node (ref "R111") (pin "1") (pinfunction "1_1") (pintype "passive"))
      (node (ref "T5") (pin "3") (pinfunction "D_3") (pintype "passive"))
    )
    (net (code "65") (name "Net-(T6-D)") (class "Default")
      (node (ref "R113") (pin "1") (pinfunction "1_1") (pintype "passive"))
      (node (ref "R114") (pin "1") (pinfunction "1_1") (pintype "passive"))
      (node (ref "R115") (pin "1") (pinfunction "1_1") (pintype "passive"))
      (node (ref "T6") (pin "3") (pinfunction "D_3") (pintype "passive"))
    )
    (net (code "66") (name "P3V3") (class "Default")
      (node (ref "C13") (pin "1") (pinfunction "1_1") (pintype "passive"))
      (node (ref "C186") (pin "1") (pinfunction "1_1") (pintype "passive"))
      (node (ref "C202") (pin "2") (pinfunction "2_2") (pintype "passive"))
      (node (ref "C297") (pin "2") (pinfunction "2_2") (pintype "passive"))
      (node (ref "C306") (pin "1") (pinfunction "1_1") (pintype "passive"))
      (node (ref "C307") (pin "1") (pinfunction "1_1") (pintype "passive"))
      (node (ref "C314") (pin "1") (pinfunction "1_1") (pintype "passive"))
      (node (ref "C315") (pin "2") (pinfunction "2_2") (pintype "passive"))
      (node (ref "C320") (pin "2") (pinfunction "2_2") (pintype "passive"))
      (node (ref "D2") (pin "2") (pinfunction "C_2") (pintype "passive"))
      (node (ref "D3") (pin "2") (pinfunction "C_2") (pintype "passive"))
      (node (ref "D4") (pin "2") (pinfunction "C_2") (pintype "passive"))
      (node (ref "D5") (pin "2") (pinfunction "C_2") (pintype "passive"))
      (node (ref "IC16") (pin "11") (pinfunction "LE_11") (pintype "input"))
      (node (ref "IC16") (pin "18") (pinfunction "VCC_18") (pintype "power_in"))
      (node (ref "IC16") (pin "25") (pinfunction "VCC_25") (pintype "power_in"))
      (node (ref "IC16") (pin "31") (pinfunction "VCC_31") (pintype "power_in"))
      (node (ref "IC16") (pin "35") (pinfunction "VCC_35") (pintype "power_in"))
      (node (ref "IC16") (pin "38") (pinfunction "VCC_38") (pintype "power_in"))
      (node (ref "IC16") (pin "42") (pinfunction "VCC_42") (pintype "power_in"))
      (node (ref "IC16") (pin "44") (pinfunction "BIASVCC_44") (pintype "input"))
      (node (ref "IC16") (pin "47") (pinfunction "VCC_47") (pintype "input"))
      (node (ref "IC16") (pin "7") (pinfunction "VCC_7") (pintype "power_in"))
      (node (ref "IC20") (pin "1") (pinfunction "VCC_1") (pintype "power_in"))
      (node (ref "L11") (pin "1") (pinfunction "1_1") (pintype "passive"))
      (node (ref "L5") (pin "1") (pinfunction "1_1") (pintype "passive"))
      (node (ref "R100") (pin "1") (pinfunction "1_1") (pintype "passive"))
      (node (ref "R400") (pin "2") (pinfunction "2_2") (pintype "passive"))
      (node (ref "R401") (pin "2") (pinfunction "2_2") (pintype "passive"))
      (node (ref "R402") (pin "2") (pinfunction "2_2") (pintype "passive"))
      (node (ref "R403") (pin "2") (pinfunction "2_2") (pintype "passive"))
      (node (ref "R404") (pin "2") (pinfunction "2_2") (pintype "passive"))
      (node (ref "R82") (pin "1") (pinfunction "1_1") (pintype "passive"))
      (node (ref "R83") (pin "1") (pinfunction "1_1") (pintype "passive"))
      (node (ref "R86") (pin "1") (pinfunction "1_1") (pintype "passive"))
      (node (ref "R89") (pin "1") (pinfunction "1_1") (pintype "passive"))
      (node (ref "R95") (pin "1") (pinfunction "1_1") (pintype "passive"))
      (node (ref "R96") (pin "1") (pinfunction "1_1") (pintype "passive"))
      (node (ref "R98") (pin "1") (pinfunction "1_1") (pintype "passive"))
      (node (ref "R99") (pin "1") (pinfunction "1_1") (pintype "passive"))
    )
    (net (code "67") (name "unconnected-(IC16-3A2-Pad12)") (class "Default")
      (node (ref "IC16") (pin "12") (pinfunction "3A2_12") (pintype "bidirectional"))
    )
    (net (code "68") (name "unconnected-(IC16-3A3-Pad13)") (class "Default")
      (node (ref "IC16") (pin "13") (pinfunction "3A3_13") (pintype "bidirectional"))
    )
    (net (code "69") (name "unconnected-(IC16-3A4-Pad16)") (class "Default")
      (node (ref "IC16") (pin "16") (pinfunction "3A4_16") (pintype "bidirectional"))
    )
    (net (code "70") (name "unconnected-(IC16-3A6-Pad20)") (class "Default")
      (node (ref "IC16") (pin "20") (pinfunction "3A6_20") (pintype "bidirectional"))
    )
    (net (code "71") (name "unconnected-(IC16-3A7-Pad22)") (class "Default")
      (node (ref "IC16") (pin "22") (pinfunction "3A7_22") (pintype "bidirectional"))
    )
    (net (code "72") (name "unconnected-(IC16-3A8-Pad23)") (class "Default")
      (node (ref "IC16") (pin "23") (pinfunction "3A8_23") (pintype "bidirectional"))
    )
    (net (code "73") (name "unconnected-(IC16-3B2-Pad37)") (class "Default")
      (node (ref "IC16") (pin "37") (pinfunction "3B2_37") (pintype "bidirectional"))
    )
    (net (code "74") (name "unconnected-(IC16-3B3-Pad36)") (class "Default")
      (node (ref "IC16") (pin "36") (pinfunction "3B3_36") (pintype "bidirectional"))
    )
    (net (code "75") (name "unconnected-(IC16-3B4-Pad33)") (class "Default")
      (node (ref "IC16") (pin "33") (pinfunction "3B4_33") (pintype "bidirectional"))
    )
    (net (code "76") (name "unconnected-(IC16-3B6-Pad29)") (class "Default")
      (node (ref "IC16") (pin "29") (pinfunction "3B6_29") (pintype "bidirectional"))
    )
    (net (code "77") (name "unconnected-(IC16-3B7-Pad27)") (class "Default")
      (node (ref "IC16") (pin "27") (pinfunction "3B7_27") (pintype "bidirectional"))
    )
    (net (code "78") (name "unconnected-(IC16-3B8-Pad26)") (class "Default")
      (node (ref "IC16") (pin "26") (pinfunction "3B8_26") (pintype "bidirectional"))
    )
  )
)
